# HEALTH_MAX86150.net
KiCad netlist of a schematic drawn in Altium Designer
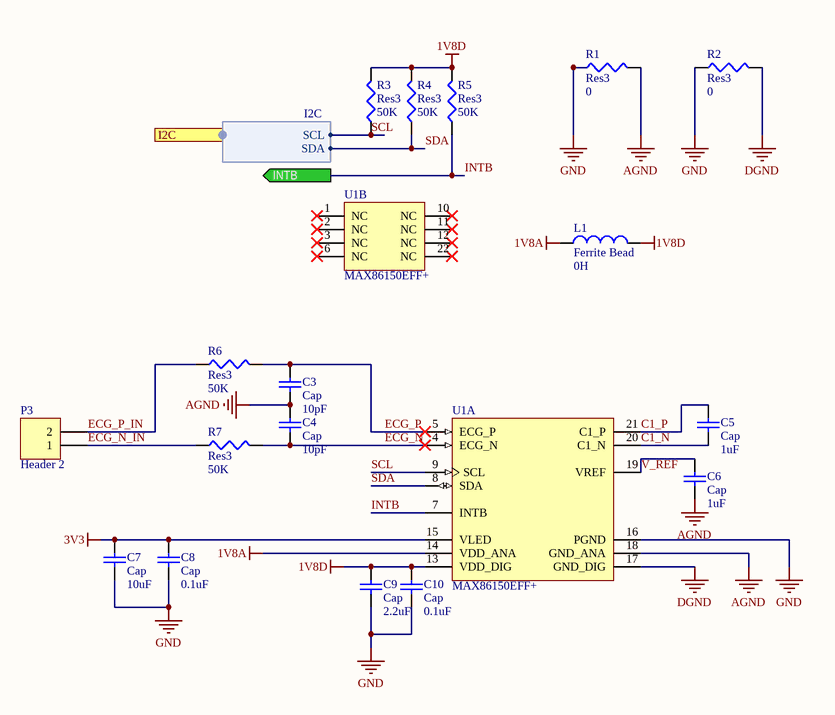
[diagram p0: HEALTH_MAX86150.SchDoc]

(export (version "E")
  (design (tool "Eeschema 10.0.6"))
  (components
    (comp (ref "C3")
      (value "Cap")
      (footprint "CAPC1005N")
      (description "Capacitor")
      (fields (field (name "ALTIUM_VALUE") "10pF") (field (name "PUBLISHER") "Altium Limited"))
      (libsource (lib "Miscellaneous Devices") (part "Cap"))
    )
    (comp (ref "C4")
      (value "Cap")
      (footprint "CAPC1005N")
      (description "Capacitor")
      (fields (field (name "ALTIUM_VALUE") "10pF") (field (name "PUBLISHER") "Altium Limited"))
      (libsource (lib "Miscellaneous Devices") (part "Cap"))
    )
    (comp (ref "C5")
      (value "Cap")
      (footprint "CAPC1005N")
      (description "Capacitor")
      (fields (field (name "ALTIUM_VALUE") "1uF") (field (name "PUBLISHER") "Altium Limited"))
      (libsource (lib "Miscellaneous Devices") (part "Cap"))
    )
    (comp (ref "C6")
      (value "Cap")
      (footprint "CAPC1005N")
      (description "Capacitor")
      (fields (field (name "ALTIUM_VALUE") "1uF") (field (name "PUBLISHER") "Altium Limited"))
      (libsource (lib "Miscellaneous Devices") (part "Cap"))
    )
    (comp (ref "C7")
      (value "Cap")
      (footprint "CAPC2012N")
      (description "Capacitor")
      (fields (field (name "ALTIUM_VALUE") "10uF") (field (name "PUBLISHER") "Altium Limited"))
      (libsource (lib "Miscellaneous Devices") (part "Cap"))
    )
    (comp (ref "C8")
      (value "Cap")
      (footprint "CAPC1005N")
      (description "Capacitor")
      (fields (field (name "ALTIUM_VALUE") "0.1uF") (field (name "PUBLISHER") "Altium Limited"))
      (libsource (lib "Miscellaneous Devices") (part "Cap"))
    )
    (comp (ref "C9")
      (value "Cap")
      (footprint "CAPC1005N")
      (description "Capacitor")
      (fields (field (name "ALTIUM_VALUE") "2.2uF") (field (name "PUBLISHER") "Altium Limited"))
      (libsource (lib "Miscellaneous Devices") (part "Cap"))
    )
    (comp (ref "C10")
      (value "Cap")
      (footprint "CAPC1005N")
      (description "Capacitor")
      (fields (field (name "ALTIUM_VALUE") "0.1uF") (field (name "PUBLISHER") "Altium Limited"))
      (libsource (lib "Miscellaneous Devices") (part "Cap"))
    )
    (comp (ref "L1")
      (value "Ferrite Bead")
      (footprint "INDC1005N")
      (description "Inductor")
      (fields (field (name "ALTIUM_VALUE") "0H") (field (name "PUBLISHER") "Altium Limited"))
      (libsource (lib "Miscellaneous Devices") (part "Inductor"))
    )
    (comp (ref "P3")
      (value "Header 2")
      (footprint "HDR1X2-PINS")
      (description "Header, 2-Pin")
      (fields (field (name "PUBLISHER") "Altium Limited"))
      (libsource (lib "Miscellaneous Connectors") (part "Header 2"))
    )
    (comp (ref "R1")
      (value "Res3")
      (footprint "RESC1005N")
      (description "Resistor")
      (fields (field (name "ALTIUM_VALUE") "0") (field (name "PUBLISHER") "Altium Limited"))
      (libsource (lib "Miscellaneous Devices") (part "Res3"))
    )
    (comp (ref "R2")
      (value "Res3")
      (footprint "RESC1005N")
      (description "Resistor")
      (fields (field (name "ALTIUM_VALUE") "0") (field (name "PUBLISHER") "Altium Limited"))
      (libsource (lib "Miscellaneous Devices") (part "Res3"))
    )
    (comp (ref "R3")
      (value "Res3")
      (footprint "RESC1005N")
      (description "Resistor")
      (fields (field (name "ALTIUM_VALUE") "50K") (field (name "PUBLISHER") "Altium Limited"))
      (libsource (lib "Miscellaneous Devices") (part "Res3"))
    )
    (comp (ref "R4")
      (value "Res3")
      (footprint "RESC1005N")
      (description "Resistor")
      (fields (field (name "ALTIUM_VALUE") "50K") (field (name "PUBLISHER") "Altium Limited"))
      (libsource (lib "Miscellaneous Devices") (part "Res3"))
    )
    (comp (ref "R5")
      (value "Res3")
      (footprint "RESC1005N")
      (description "Resistor")
      (fields (field (name "ALTIUM_VALUE") "50K") (field (name "PUBLISHER") "Altium Limited"))
      (libsource (lib "Miscellaneous Devices") (part "Res3"))
    )
    (comp (ref "R6")
      (value "Res3")
      (footprint "RESC1005N")
      (description "Resistor")
      (fields (field (name "ALTIUM_VALUE") "50K") (field (name "PUBLISHER") "Altium Limited"))
      (libsource (lib "Miscellaneous Devices") (part "Res3"))
    )
    (comp (ref "R7")
      (value "Res3")
      (footprint "RESC1005N")
      (description "Resistor")
      (fields (field (name "ALTIUM_VALUE") "50K") (field (name "PUBLISHER") "Altium Limited"))
      (libsource (lib "Miscellaneous Devices") (part "Res3"))
    )
    (comp (ref "U1")
      (value "MAX86150EFF+")
      (footprint "MAXM-OESIP-22_V")
      (fields (field (name "MANUFACTURER") "Maxim"))
      (libsource (lib "Altium Content Vault") (part "MAXM-MAX86150-OESIP-22"))
    )
  )
  (nets
    (net (code "2") (name "/C1_N") (class "Default")
      (node (ref "C5") (pin "1") (pinfunction "1_1") (pintype "passive"))
      (node (ref "U1") (pin "20") (pinfunction "C1_N_20") (pintype "passive"))
    )
    (net (code "3") (name "/C1_P") (class "Default")
      (node (ref "C5") (pin "2") (pinfunction "2_2") (pintype "passive"))
      (node (ref "U1") (pin "21") (pinfunction "C1_P_21") (pintype "passive"))
    )
    (net (code "4") (name "/ECG_N") (class "Default")
      (node (ref "C4") (pin "1") (pinfunction "1_1") (pintype "passive"))
      (node (ref "R7") (pin "2") (pinfunction "2_2") (pintype "passive"))
      (node (ref "U1") (pin "4") (pinfunction "ECG_N_4") (pintype "input"))
    )
    (net (code "5") (name "/ECG_N_IN") (class "Default")
      (node (ref "P3") (pin "1") (pinfunction "1_1") (pintype "passive"))
      (node (ref "R7") (pin "1") (pinfunction "1_1") (pintype "passive"))
    )
    (net (code "6") (name "/ECG_P") (class "Default")
      (node (ref "C3") (pin "2") (pinfunction "2_2") (pintype "passive"))
      (node (ref "R6") (pin "2") (pinfunction "2_2") (pintype "passive"))
      (node (ref "U1") (pin "5") (pinfunction "ECG_P_5") (pintype "input"))
    )
    (net (code "7") (name "/ECG_P_IN") (class "Default")
      (node (ref "P3") (pin "2") (pinfunction "2_2") (pintype "passive"))
      (node (ref "R6") (pin "1") (pinfunction "1_1") (pintype "passive"))
    )
    (net (code "8") (name "/INTB") (class "Default")
      (node (ref "R5") (pin "1") (pinfunction "1_1") (pintype "passive"))
      (node (ref "U1") (pin "7") (pinfunction "INTB_7") (pintype "open_collector"))
    )
    (net (code "9") (name "/SCL") (class "Default")
      (node (ref "R3") (pin "1") (pinfunction "1_1") (pintype "passive"))
      (node (ref "U1") (pin "9") (pinfunction "SCL_9") (pintype "input"))
    )
    (net (code "10") (name "/SDA") (class "Default")
      (node (ref "R4") (pin "1") (pinfunction "1_1") (pintype "passive"))
      (node (ref "U1") (pin "8") (pinfunction "SDA_8") (pintype "bidirectional"))
    )
    (net (code "11") (name "/V_REF") (class "Default")
      (node (ref "C6") (pin "2") (pinfunction "2_2") (pintype "passive"))
      (node (ref "U1") (pin "19") (pinfunction "VREF_19") (pintype "passive"))
    )
    (net (code "13") (name "1V8A") (class "Default")
      (node (ref "L1") (pin "1") (pinfunction "1_1") (pintype "passive"))
      (node (ref "U1") (pin "14") (pinfunction "VDD_ANA_14") (pintype "power_in"))
    )
    (net (code "14") (name "1V8D") (class "Default")
      (node (ref "C10") (pin "2") (pinfunction "2_2") (pintype "passive"))
      (node (ref "C9") (pin "2") (pinfunction "2_2") (pintype "passive"))
      (node (ref "L1") (pin "2") (pinfunction "2_2") (pintype "passive"))
      (node (ref "R3") (pin "2") (pinfunction "2_2") (pintype "passive"))
      (node (ref "R4") (pin "2") (pinfunction "2_2") (pintype "passive"))
      (node (ref "R5") (pin "2") (pinfunction "2_2") (pintype "passive"))
      (node (ref "U1") (pin "13") (pinfunction "VDD_DIG_13") (pintype "power_in"))
    )
    (net (code "15") (name "3V3") (class "Default")
      (node (ref "C7") (pin "2") (pinfunction "2_2") (pintype "passive"))
      (node (ref "C8") (pin "2") (pinfunction "2_2") (pintype "passive"))
      (node (ref "U1") (pin "15") (pinfunction "VLED_15") (pintype "power_in"))
    )
    (net (code "16") (name "AGND") (class "Default")
      (node (ref "C3") (pin "1") (pinfunction "1_1") (pintype "passive"))
      (node (ref "C4") (pin "2") (pinfunction "2_2") (pintype "passive"))
      (node (ref "C6") (pin "1") (pinfunction "1_1") (pintype "passive"))
      (node (ref "R1") (pin "2") (pinfunction "2_2") (pintype "passive"))
      (node (ref "U1") (pin "18") (pinfunction "GND_ANA_18") (pintype "power_in"))
    )
    (net (code "17") (name "DGND") (class "Default")
      (node (ref "R2") (pin "2") (pinfunction "2_2") (pintype "passive"))
      (node (ref "U1") (pin "17") (pinfunction "GND_DIG_17") (pintype "power_in"))
    )
    (net (code "18") (name "GND") (class "Default")
      (node (ref "C10") (pin "1") (pinfunction "1_1") (pintype "passive"))
      (node (ref "C7") (pin "1") (pinfunction "1_1") (pintype "passive"))
      (node (ref "C8") (pin "1") (pinfunction "1_1") (pintype "passive"))
      (node (ref "C9") (pin "1") (pinfunction "1_1") (pintype "passive"))
      (node (ref "R1") (pin "1") (pinfunction "1_1") (pintype "passive"))
      (node (ref "R2") (pin "1") (pinfunction "1_1") (pintype "passive"))
      (node (ref "U1") (pin "16") (pinfunction "PGND_16") (pintype "power_in"))
    )
    (net (code "19") (name "unconnected-(U1B-NC-Pad1)") (class "Default")
      (node (ref "U1") (pin "1") (pinfunction "NC_1") (pintype "passive+no_connect"))
    )
    (net (code "20") (name "unconnected-(U1B-NC-Pad2)") (class "Default")
      (node (ref "U1") (pin "2") (pinfunction "NC_2") (pintype "passive+no_connect"))
    )
    (net (code "21") (name "unconnected-(U1B-NC-Pad3)") (class "Default")
      (node (ref "U1") (pin "3") (pinfunction "NC_3") (pintype "passive+no_connect"))
    )
    (net (code "22") (name "unconnected-(U1B-NC-Pad6)") (class "Default")
      (node (ref "U1") (pin "6") (pinfunction "NC_6") (pintype "passive+no_connect"))
    )
    (net (code "23") (name "unconnected-(U1B-NC-Pad10)") (class "Default")
      (node (ref "U1") (pin "10") (pinfunction "NC_10") (pintype "passive+no_connect"))
    )
    (net (code "24") (name "unconnected-(U1B-NC-Pad11)") (class "Default")
      (node (ref "U1") (pin "11") (pinfunction "NC_11") (pintype "passive+no_connect"))
    )
    (net (code "25") (name "unconnected-(U1B-NC-Pad12)") (class "Default")
      (node (ref "U1") (pin "12") (pinfunction "NC_12") (pintype "passive+no_connect"))
    )
    (net (code "26") (name "unconnected-(U1B-NC-Pad22)") (class "Default")
      (node (ref "U1") (pin "22") (pinfunction "NC_22") (pintype "passive+no_connect"))
    )
  )
)
